# 36V_Supply.net
KiCad netlist of a schematic drawn in Altium Designer
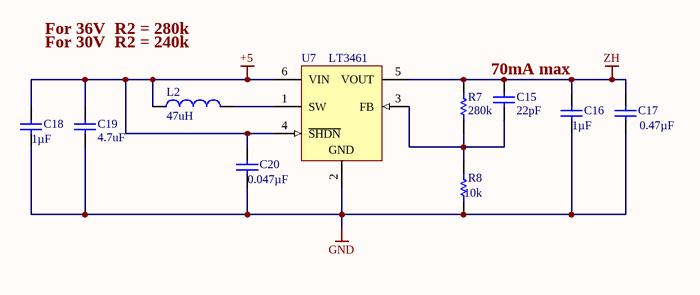
[diagram p0: 36V_Supply.SchDoc]

(export (version "E")
  (design (tool "Eeschema 10.0.6"))
  (components
    (comp (ref "C15")
      (value "22pF")
      (footprint "CAPC1206(3216)170_L")
      (description "CAP CER 22PF 50V C0G/NP0 1206")
      (fields
        (field (name "MANUFACTURER") "KEMET")
        (field (name "MANUFACTURER PART NUMBER") "C1206C220K5GACTU")
      )
      (libsource (lib "Altium Content Vault") (part "CMP-1037-04573-1"))
    )
    (comp (ref "C16")
      (value "CAP CER 1UF 50V X7R 1210")
      (footprint "CAPC1210(3225)100_N")
      (fields
        (field (name "MANUFACTURER") "Taiyo Yuden")
        (field (name "MANUFACTURER PART NUMBER") "UMK325B7105KH-T")
        (field (name "CAPACITANCE") "1µF")
        (field (name "TOLERANCE") "±10%")
      )
      (libsource (lib "Altium Content Vault") (part "CMP-1038-01123-1"))
    )
    (comp (ref "C17")
      (value "CAP CER 0.47UF 50V X7R 1206")
      (footprint "CAPC1206(3216)190_N")
      (fields
        (field (name "MANUFACTURER") "Taiyo Yuden")
        (field (name "MANUFACTURER PART NUMBER") "UMK316B7474KL-T")
        (field (name "CAPACITANCE") "0.47µF")
        (field (name "TOLERANCE") "±10%")
      )
      (libsource (lib "Altium Content Vault") (part "CMP-1037-04570-1"))
    )
    (comp (ref "C18")
      (value "CAP CER 1UF 16V X7R 0805")
      (footprint "CAPC0805(2012)145_N")
      (fields
        (field (name "MANUFACTURER") "Taiyo Yuden")
        (field (name "MANUFACTURER PART NUMBER") "EMK212B7105KG-T")
        (field (name "CAPACITANCE") "1µF")
        (field (name "TOLERANCE") "±10%")
      )
      (libsource (lib "Altium Content Vault") (part "CMP-1036-04795-1"))
    )
    (comp (ref "C19")
      (value "4.7uF")
      (footprint "CAPC0805(2012)145_M")
      (description "CAP CER 4.7UF 16V X7R 0805")
      (fields
        (field (name "MANUFACTURER") "KEMET")
        (field (name "MANUFACTURER PART NUMBER") "C0805C475K4RACTU")
      )
      (libsource (lib "Altium Content Vault") (part "CMP-1036-04750-1"))
    )
    (comp (ref "C20")
      (value "CAP CER 0.047UF 16V X7R 0603")
      (footprint "CAPC0805(2012)145_N")
      (fields
        (field (name "MANUFACTURER") "Murata Electronics North America")
        (field (name "MANUFACTURER PART NUMBER") "GRM188R71C473KA01D")
        (field (name "CAPACITANCE") "0.047µF")
        (field (name "TOLERANCE") "±10%")
      )
      (libsource (lib "Altium Content Vault") (part "CMP-1036-04795-1"))
    )
    (comp (ref "L2")
      (value "47uH")
      (footprint "C1210")
      (description "FIXED IND 47UH 170MA 1.3 OHM SMD")
      (fields
        (field (name "MANUFACTURER") "Murata Electronics North America")
        (field (name "MANUFACTURER PART NUMBER") "LQH32CN470K23L")
      )
      (libsource (lib "Miscellaneous Devices") (part "Inductor"))
    )
    (comp (ref "R7")
      (value "RES SMD 280K OHM 1% 1/8W 0805")
      (footprint "RESC0805(2012)_M")
      (fields
        (field (name "MANUFACTURER") "Vishay Dale")
        (field (name "MANUFACTURER PART NUMBER") "CRCW0805280KFKEA")
        (field (name "RESISTANCE (OHMS)") "280k")
        (field (name "TOLERANCE") "±1%")
      )
      (libsource (lib "Altium Content Vault") (part "CMP-1013-00017-1"))
    )
    (comp (ref "R8")
      (value "RES SMD 10K OHM 1% 1/8W 0805")
      (footprint "RESC0805(2012)_M")
      (fields
        (field (name "MANUFACTURER") "Yageo")
        (field (name "MANUFACTURER PART NUMBER") "RC0805FR-0710KL")
        (field (name "RESISTANCE (OHMS)") "10k")
        (field (name "TOLERANCE") "±1%")
      )
      (libsource (lib "Altium Content Vault") (part "CMP-1013-00017-1"))
    )
    (comp (ref "U7")
      (value "LT3461")
      (footprint "LT-S6-6-TSOT-23_N")
      (description "IC REG BOOST ADJ 0.3A TSOT23-6")
      (libsource (lib "Altium Content Vault") (part "CMP-0491-01698-1"))
    )
  )
  (nets
    (net (code "1") (name "+5") (class "Default")
      (node (ref "C18") (pin "2") (pinfunction "2_2") (pintype "passive"))
      (node (ref "C19") (pin "2") (pinfunction "2_2") (pintype "passive"))
      (node (ref "C20") (pin "2") (pinfunction "2_2") (pintype "passive"))
      (node (ref "L2") (pin "1") (pinfunction "1_1") (pintype "passive"))
      (node (ref "U7") (pin "4") (pinfunction "~{SHDN}_4") (pintype "input"))
      (node (ref "U7") (pin "6") (pinfunction "VIN_6") (pintype "power_in"))
    )
    (net (code "2") (name "GND") (class "Default")
      (node (ref "C16") (pin "1") (pinfunction "1_1") (pintype "passive"))
      (node (ref "C17") (pin "1") (pinfunction "1_1") (pintype "passive"))
      (node (ref "C18") (pin "1") (pinfunction "1_1") (pintype "passive"))
      (node (ref "C19") (pin "1") (pinfunction "1_1") (pintype "passive"))
      (node (ref "C20") (pin "1") (pinfunction "1_1") (pintype "passive"))
      (node (ref "R8") (pin "2") (pinfunction "2_2") (pintype "passive"))
      (node (ref "U7") (pin "2") (pinfunction "GND_2") (pintype "power_in"))
    )
    (net (code "3") (name "Net-(U7-FB)") (class "Default")
      (node (ref "C15") (pin "1") (pinfunction "1_1") (pintype "passive"))
      (node (ref "R7") (pin "2") (pinfunction "2_2") (pintype "passive"))
      (node (ref "R8") (pin "1") (pinfunction "1_1") (pintype "passive"))
      (node (ref "U7") (pin "3") (pinfunction "FB_3") (pintype "input"))
    )
    (net (code "4") (name "Net-(U7-SW)") (class "Default")
      (node (ref "L2") (pin "2") (pinfunction "2_2") (pintype "passive"))
      (node (ref "U7") (pin "1") (pinfunction "SW_1") (pintype "passive"))
    )
    (net (code "5") (name "ZH") (class "Default")
      (node (ref "C15") (pin "2") (pinfunction "2_2") (pintype "passive"))
      (node (ref "C16") (pin "2") (pinfunction "2_2") (pintype "passive"))
      (node (ref "C17") (pin "2") (pinfunction "2_2") (pintype "passive"))
      (node (ref "R7") (pin "1") (pinfunction "1_1") (pintype "passive"))
      (node (ref "U7") (pin "5") (pinfunction "VOUT_5") (pintype "power_in"))
    )
  )
)
